# Connectors.net
KiCad netlist of a schematic drawn in Altium Designer
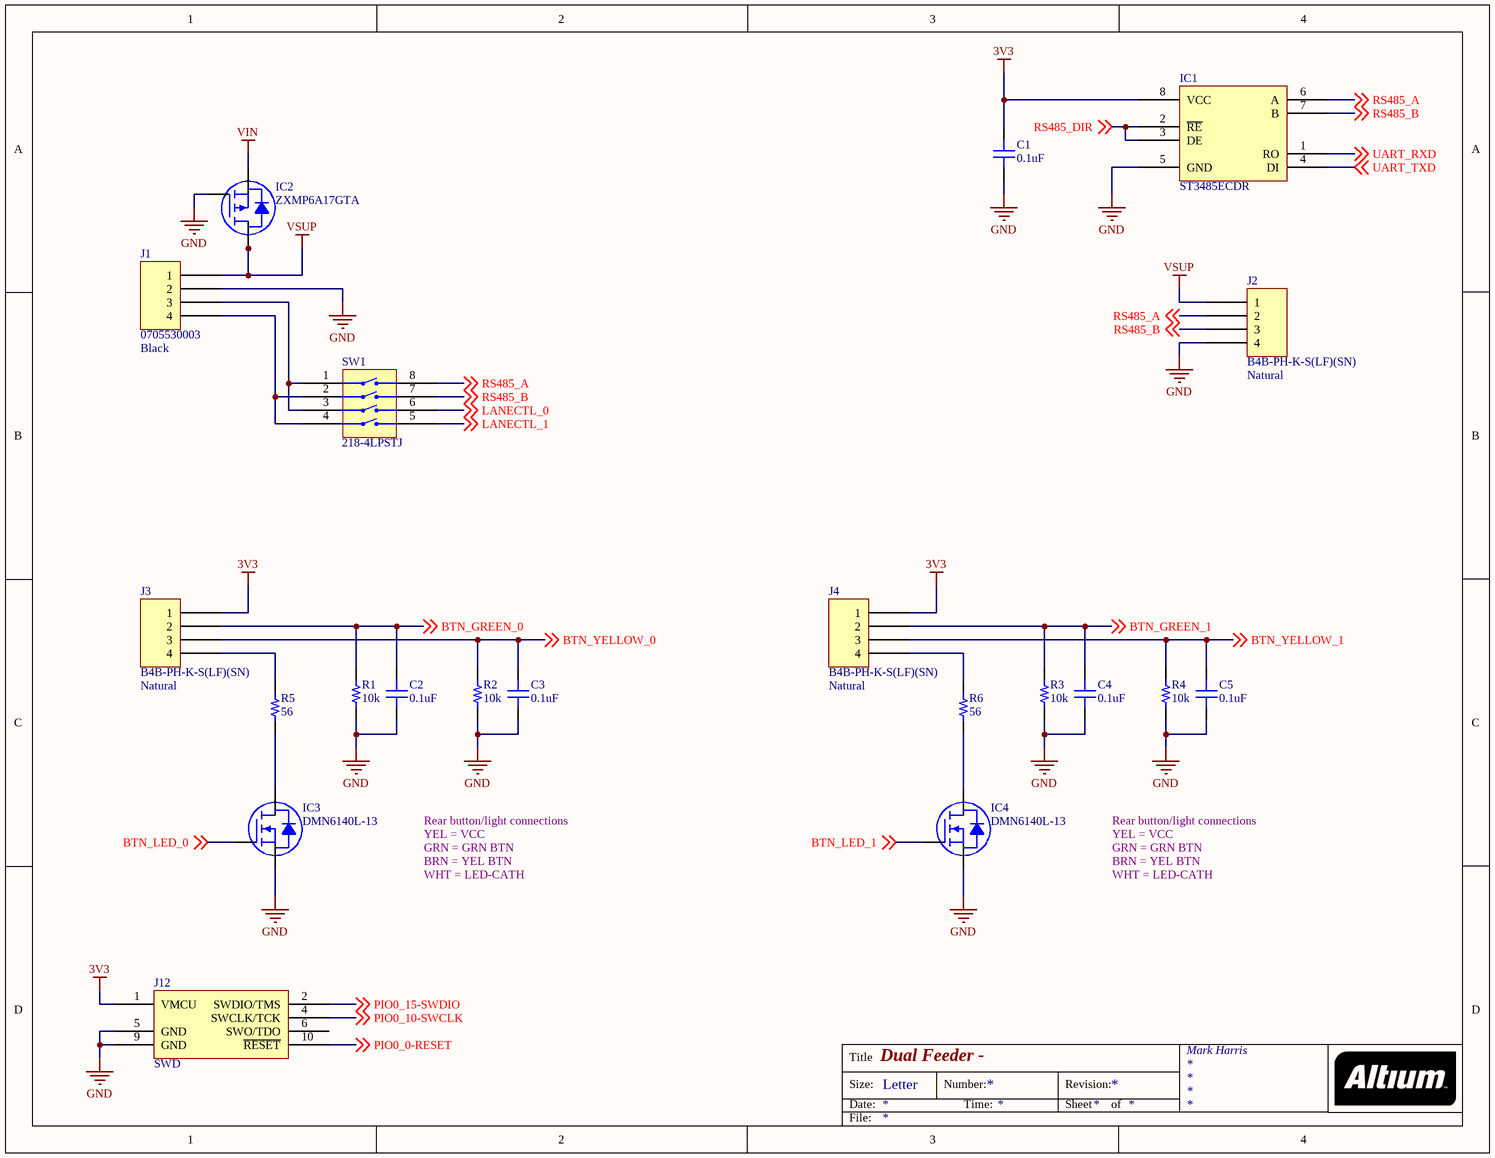
[diagram p0: Connectors.SchDoc]

(export (version "E")
  (design (tool "Eeschema 10.0.6"))
  (components
    (comp (ref "C1")
      (value "0.1uF")
      (footprint "CAP 0603/1608")
      (description "CAP CER 0.1UF 50V X7R 0603")
      (fields
        (field (name "PART NUMBER") "CL10B104JB8NNNC")
        (field (name "MANUFACTURER") "Samsung Electro-Mechanics America, Inc.")
      )
      (libsource (lib "Celestial Library Database") (part "Capacitor"))
    )
    (comp (ref "C2")
      (value "0.1uF")
      (footprint "CAP 0603/1608")
      (description "CAP CER 0.1UF 50V X7R 0603")
      (fields
        (field (name "PART NUMBER") "CL10B104JB8NNNC")
        (field (name "MANUFACTURER") "Samsung Electro-Mechanics America, Inc.")
      )
      (libsource (lib "Celestial Library Database") (part "Capacitor"))
    )
    (comp (ref "C3")
      (value "0.1uF")
      (footprint "CAP 0603/1608")
      (description "CAP CER 0.1UF 50V X7R 0603")
      (fields
        (field (name "PART NUMBER") "CL10B104JB8NNNC")
        (field (name "MANUFACTURER") "Samsung Electro-Mechanics America, Inc.")
      )
      (libsource (lib "Celestial Library Database") (part "Capacitor"))
    )
    (comp (ref "C4")
      (value "0.1uF")
      (footprint "CAP 0603/1608")
      (description "CAP CER 0.1UF 50V X7R 0603")
      (fields
        (field (name "PART NUMBER") "CL10B104JB8NNNC")
        (field (name "MANUFACTURER") "Samsung Electro-Mechanics America, Inc.")
      )
      (libsource (lib "Celestial Library Database") (part "Capacitor"))
    )
    (comp (ref "C5")
      (value "0.1uF")
      (footprint "CAP 0603/1608")
      (description "CAP CER 0.1UF 50V X7R 0603")
      (fields
        (field (name "PART NUMBER") "CL10B104JB8NNNC")
        (field (name "MANUFACTURER") "Samsung Electro-Mechanics America, Inc.")
      )
      (libsource (lib "Celestial Library Database") (part "Capacitor"))
    )
    (comp (ref "IC1")
      (value "ST3485ECDR")
      (footprint "ST SOIC-8N")
      (description "IC TXRX RS422/485 15MBPS 8SO")
      (fields (field (name "MANUFACTURER") "STMicroelectronics"))
      (libsource (lib "Celestial Library Database") (part "ST ST3485Ex"))
    )
    (comp (ref "IC2")
      (value "ZXMP6A17GTA")
      (footprint "DIODES SOT-223")
      (description "MOSFET P-CH 60V 3A SOT223")
      (fields (field (name "MANUFACTURER") "Diodes Incorporated"))
      (libsource (lib "Celestial Library Database") (part "DIODES MOSFET P-CH SOT-223"))
    )
    (comp (ref "IC3")
      (value "DMN6140L-13")
      (footprint "DIODES SOT-23-3")
      (description "MOSFET N-CH 60V 1.6A SOT23")
      (fields (field (name "MANUFACTURER") "Diodes Incorporated"))
      (libsource (lib "Celestial Library Database") (part "DIODES INC MOSFET N-CH SOT-23-3"))
    )
    (comp (ref "IC4")
      (value "DMN6140L-13")
      (footprint "DIODES SOT-23-3")
      (description "MOSFET N-CH 60V 1.6A SOT23")
      (fields (field (name "MANUFACTURER") "Diodes Incorporated"))
      (libsource (lib "Celestial Library Database") (part "DIODES INC MOSFET N-CH SOT-23-3"))
    )
    (comp (ref "J1")
      (value "0705530003")
      (footprint "MOLEX SDA-70553-4PIN")
      (description "CONN HEADER 4POS .100 R/A GOLD")
      (fields (field (name "COLOUR") "Black") (field (name "MANUFACTURER") "Molex, LLC"))
      (libsource (lib "") (part "4 Pin_1"))
    )
    (comp (ref "J2")
      (value "B4B-PH-K-S(LF)(SN)")
      (footprint "JST B4B-PH-K")
      (description "CONN HEADER PH TOP 4POS 2MM")
      (fields (field (name "COLOUR") "Natural") (field (name "MANUFACTURER") "JST Sales America Inc."))
      (libsource (lib "Celestial Library Database") (part "4 Pin"))
    )
    (comp (ref "J3")
      (value "B4B-PH-K-S(LF)(SN)")
      (footprint "JST B4B-PH-K")
      (description "CONN HEADER PH TOP 4POS 2MM")
      (fields (field (name "COLOUR") "Natural") (field (name "MANUFACTURER") "JST Sales America Inc."))
      (libsource (lib "") (part "4 Pin_1"))
    )
    (comp (ref "J4")
      (value "B4B-PH-K-S(LF)(SN)")
      (footprint "JST B4B-PH-K")
      (description "CONN HEADER PH TOP 4POS 2MM")
      (fields (field (name "COLOUR") "Natural") (field (name "MANUFACTURER") "JST Sales America Inc."))
      (libsource (lib "") (part "4 Pin_1"))
    )
    (comp (ref "J12") (value "SWD") (footprint "10 Pin SWD") (libsource (lib "Head Sensor") (part "SWD")))
    (comp (ref "R1")
      (value "10k")
      (footprint "RES 0603/1608")
      (description "RES SMD 10K OHM 5% 1/10W 0603")
      (fields
        (field (name "PART NUMBER") "ERJ-3GEYJ103V")
        (field (name "MANUFACTURER") "Panasonic Electronic Components")
      )
      (libsource (lib "Celestial Library Database") (part "Resistor"))
    )
    (comp (ref "R2")
      (value "10k")
      (footprint "RES 0603/1608")
      (description "RES SMD 10K OHM 5% 1/10W 0603")
      (fields
        (field (name "PART NUMBER") "ERJ-3GEYJ103V")
        (field (name "MANUFACTURER") "Panasonic Electronic Components")
      )
      (libsource (lib "Celestial Library Database") (part "Resistor"))
    )
    (comp (ref "R3")
      (value "10k")
      (footprint "RES 0603/1608")
      (description "RES SMD 10K OHM 5% 1/10W 0603")
      (fields
        (field (name "PART NUMBER") "ERJ-3GEYJ103V")
        (field (name "MANUFACTURER") "Panasonic Electronic Components")
      )
      (libsource (lib "Celestial Library Database") (part "Resistor"))
    )
    (comp (ref "R4")
      (value "10k")
      (footprint "RES 0603/1608")
      (description "RES SMD 10K OHM 5% 1/10W 0603")
      (fields
        (field (name "PART NUMBER") "ERJ-3GEYJ103V")
        (field (name "MANUFACTURER") "Panasonic Electronic Components")
      )
      (libsource (lib "Celestial Library Database") (part "Resistor"))
    )
    (comp (ref "R5")
      (value "56")
      (footprint "RES 0603/1608")
      (description "RES SMD 56 OHM 5% 1/10W 0603")
      (fields
        (field (name "PART NUMBER") "ERJ-3GEYJ560V")
        (field (name "MANUFACTURER") "Panasonic Electronic Components")
      )
      (libsource (lib "Celestial Library Database") (part "Resistor"))
    )
    (comp (ref "R6")
      (value "56")
      (footprint "RES 0603/1608")
      (description "RES SMD 56 OHM 5% 1/10W 0603")
      (fields
        (field (name "PART NUMBER") "ERJ-3GEYJ560V")
        (field (name "MANUFACTURER") "Panasonic Electronic Components")
      )
      (libsource (lib "Celestial Library Database") (part "Resistor"))
    )
    (comp (ref "SW1")
      (value "218-4LPSTJ")
      (footprint "CTS 218-4LPJ")
      (description "SWITCH SLIDE DIP 4POS SPST 25MA 24V")
      (fields (field (name "MANUFACTURER") "CTS Electrocomponents") (field (name "VOLTAGE") "24VDC"))
      (libsource (lib "Celestial Library Database") (part "DIP SW 4P"))
    )
  )
  (nets
    (net (code "1") (name "3V3") (class "Default")
      (node (ref "C1") (pin "1") (pinfunction "1_1") (pintype "passive"))
      (node (ref "IC1") (pin "8") (pinfunction "VCC_8") (pintype "passive"))
      (node (ref "J12") (pin "1") (pinfunction "VMCU_1") (pintype "passive"))
      (node (ref "J3") (pin "1") (pinfunction "1_1") (pintype "passive"))
      (node (ref "J4") (pin "1") (pinfunction "1_1") (pintype "passive"))
    )
    (net (code "2") (name "BTN_GREEN_0") (class "Default")
      (node (ref "C2") (pin "1") (pinfunction "1_1") (pintype "passive"))
      (node (ref "J3") (pin "2") (pinfunction "2_2") (pintype "passive"))
      (node (ref "R1") (pin "2") (pinfunction "2_2") (pintype "passive"))
    )
    (net (code "3") (name "BTN_GREEN_1") (class "Default")
      (node (ref "C4") (pin "1") (pinfunction "1_1") (pintype "passive"))
      (node (ref "J4") (pin "2") (pinfunction "2_2") (pintype "passive"))
      (node (ref "R3") (pin "2") (pinfunction "2_2") (pintype "passive"))
    )
    (net (code "4") (name "BTN_LED_0") (class "Default")
      (node (ref "IC3") (pin "1") (pinfunction "G_1") (pintype "passive"))
    )
    (net (code "5") (name "BTN_LED_1") (class "Default")
      (node (ref "IC4") (pin "1") (pinfunction "G_1") (pintype "passive"))
    )
    (net (code "6") (name "BTN_YELLOW_0") (class "Default")
      (node (ref "C3") (pin "1") (pinfunction "1_1") (pintype "passive"))
      (node (ref "J3") (pin "3") (pinfunction "3_3") (pintype "passive"))
      (node (ref "R2") (pin "2") (pinfunction "2_2") (pintype "passive"))
    )
    (net (code "7") (name "BTN_YELLOW_1") (class "Default")
      (node (ref "C5") (pin "1") (pinfunction "1_1") (pintype "passive"))
      (node (ref "J4") (pin "3") (pinfunction "3_3") (pintype "passive"))
      (node (ref "R4") (pin "2") (pinfunction "2_2") (pintype "passive"))
    )
    (net (code "8") (name "GND") (class "Default")
      (node (ref "C1") (pin "2") (pinfunction "2_2") (pintype "passive"))
      (node (ref "C2") (pin "2") (pinfunction "2_2") (pintype "passive"))
      (node (ref "C3") (pin "2") (pinfunction "2_2") (pintype "passive"))
      (node (ref "C4") (pin "2") (pinfunction "2_2") (pintype "passive"))
      (node (ref "C5") (pin "2") (pinfunction "2_2") (pintype "passive"))
      (node (ref "IC1") (pin "5") (pinfunction "GND_5") (pintype "passive"))
      (node (ref "IC2") (pin "1") (pinfunction "G_1") (pintype "passive"))
      (node (ref "IC3") (pin "3") (pinfunction "S_3") (pintype "passive"))
      (node (ref "IC4") (pin "3") (pinfunction "S_3") (pintype "passive"))
      (node (ref "J1") (pin "2") (pinfunction "2_2") (pintype "passive"))
      (node (ref "J12") (pin "5") (pinfunction "GND_5") (pintype "passive"))
      (node (ref "J12") (pin "9") (pinfunction "GND_9") (pintype "passive"))
      (node (ref "J2") (pin "4") (pinfunction "4_4") (pintype "passive"))
      (node (ref "R1") (pin "1") (pinfunction "1_1") (pintype "passive"))
      (node (ref "R2") (pin "1") (pinfunction "1_1") (pintype "passive"))
      (node (ref "R3") (pin "1") (pinfunction "1_1") (pintype "passive"))
      (node (ref "R4") (pin "1") (pinfunction "1_1") (pintype "passive"))
    )
    (net (code "9") (name "LANECTL_0") (class "Default")
      (node (ref "SW1") (pin "6") (pinfunction "6_6") (pintype "passive"))
    )
    (net (code "10") (name "LANECTL_1") (class "Default")
      (node (ref "SW1") (pin "5") (pinfunction "5_5") (pintype "passive"))
    )
    (net (code "11") (name "Net-(IC3-D)") (class "Default")
      (node (ref "IC3") (pin "2") (pinfunction "D_2") (pintype "passive"))
      (node (ref "R5") (pin "1") (pinfunction "1_1") (pintype "passive"))
    )
    (net (code "12") (name "Net-(IC4-D)") (class "Default")
      (node (ref "IC4") (pin "2") (pinfunction "D_2") (pintype "passive"))
      (node (ref "R6") (pin "1") (pinfunction "1_1") (pintype "passive"))
    )
    (net (code "13") (name "Net-(J1-Pad3)") (class "Default")
      (node (ref "J1") (pin "3") (pinfunction "3_3") (pintype "passive"))
      (node (ref "SW1") (pin "1") (pinfunction "GND_1") (pintype "passive"))
      (node (ref "SW1") (pin "3") (pinfunction "GND_3") (pintype "passive"))
    )
    (net (code "14") (name "Net-(J1-Pad4)") (class "Default")
      (node (ref "J1") (pin "4") (pinfunction "4_4") (pintype "passive"))
      (node (ref "SW1") (pin "2") (pinfunction "GND_2") (pintype "passive"))
      (node (ref "SW1") (pin "4") (pinfunction "GND_4") (pintype "passive"))
    )
    (net (code "15") (name "Net-(J3-Pad4)") (class "Default")
      (node (ref "J3") (pin "4") (pinfunction "4_4") (pintype "passive"))
      (node (ref "R5") (pin "2") (pinfunction "2_2") (pintype "passive"))
    )
    (net (code "16") (name "Net-(J4-Pad4)") (class "Default")
      (node (ref "J4") (pin "4") (pinfunction "4_4") (pintype "passive"))
      (node (ref "R6") (pin "2") (pinfunction "2_2") (pintype "passive"))
    )
    (net (code "17") (name "PIO0_0-RESET") (class "Default")
      (node (ref "J12") (pin "10") (pinfunction "~{RESET}_10") (pintype "passive"))
    )
    (net (code "18") (name "PIO0_10-SWCLK") (class "Default")
      (node (ref "J12") (pin "4") (pinfunction "SWCLK/TCK_4") (pintype "passive"))
    )
    (net (code "19") (name "PIO0_15-SWDIO") (class "Default")
      (node (ref "J12") (pin "2") (pinfunction "SWDIO/TMS_2") (pintype "passive"))
    )
    (net (code "20") (name "RS485_A") (class "Default")
      (node (ref "IC1") (pin "6") (pinfunction "A_6") (pintype "passive"))
      (node (ref "J2") (pin "2") (pinfunction "2_2") (pintype "passive"))
      (node (ref "SW1") (pin "8") (pinfunction "8_8") (pintype "passive"))
    )
    (net (code "21") (name "RS485_B") (class "Default")
      (node (ref "IC1") (pin "7") (pinfunction "B_7") (pintype "passive"))
      (node (ref "J2") (pin "3") (pinfunction "3_3") (pintype "passive"))
      (node (ref "SW1") (pin "7") (pinfunction "7_7") (pintype "passive"))
    )
    (net (code "22") (name "RS485_DIR") (class "Default")
      (node (ref "IC1") (pin "2") (pinfunction "~{RE}_2") (pintype "passive"))
      (node (ref "IC1") (pin "3") (pinfunction "DE_3") (pintype "passive"))
    )
    (net (code "23") (name "UART_RXD") (class "Default")
      (node (ref "IC1") (pin "1") (pinfunction "RO_1") (pintype "passive"))
    )
    (net (code "24") (name "UART_TXD") (class "Default")
      (node (ref "IC1") (pin "4") (pinfunction "DI_4") (pintype "passive"))
    )
    (net (code "25") (name "VIN") (class "Default")
      (node (ref "IC2") (pin "3") (pinfunction "S_3") (pintype "passive"))
    )
    (net (code "26") (name "VSUP") (class "Default")
      (node (ref "IC2") (pin "2") (pinfunction "D_2") (pintype "passive"))
      (node (ref "IC2") (pin "4") (pinfunction "D_4") (pintype "passive"))
      (node (ref "J1") (pin "1") (pinfunction "1_1") (pintype "passive"))
      (node (ref "J2") (pin "1") (pinfunction "1_1") (pintype "passive"))
    )
    (net (code "27") (name "unconnected-(J12-SWO{slash}TDO-Pad6)") (class "Default")
      (node (ref "J12") (pin "6") (pinfunction "SWO/TDO_6") (pintype "passive"))
    )
  )
)
